# charlieplex12.net
KiCad netlist of a schematic drawn in EAGLE
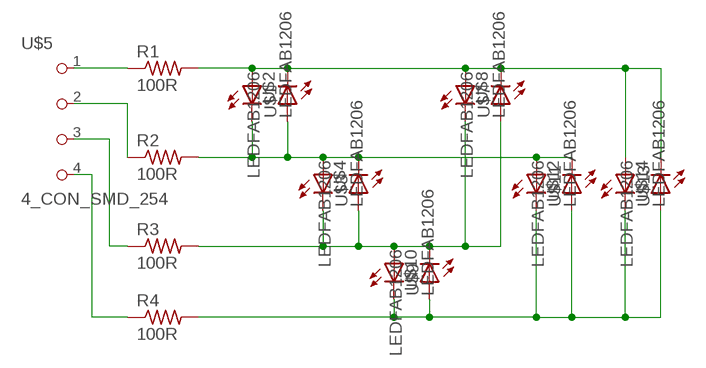
[diagram p0: schematic, sheet 1]

(export (version "E")
  (design (tool "Eeschema 10.0.6"))
  (components
    (comp (ref "R1")
      (value "100R")
      (footprint "eagle-import:R1206FAB")
      (libsource (lib "eagle-import") (part "RES-US1206FAB"))
    )
    (comp (ref "R2")
      (value "100R")
      (footprint "eagle-import:R1206FAB")
      (libsource (lib "eagle-import") (part "RES-US1206FAB"))
    )
    (comp (ref "R3")
      (value "100R")
      (footprint "eagle-import:R1206FAB")
      (libsource (lib "eagle-import") (part "RES-US1206FAB"))
    )
    (comp (ref "R4")
      (value "100R")
      (footprint "eagle-import:R1206FAB")
      (libsource (lib "eagle-import") (part "RES-US1206FAB"))
    )
    (comp (ref "U$1")
      (value "LEDFAB1206")
      (footprint "eagle-import:LED1206FAB")
      (libsource (lib "eagle-import") (part "LEDFAB1206"))
    )
    (comp (ref "U$2")
      (value "LEDFAB1206")
      (footprint "eagle-import:LED1206FAB")
      (libsource (lib "eagle-import") (part "LEDFAB1206"))
    )
    (comp (ref "U$3")
      (value "LEDFAB1206")
      (footprint "eagle-import:LED1206FAB")
      (libsource (lib "eagle-import") (part "LEDFAB1206"))
    )
    (comp (ref "U$4")
      (value "LEDFAB1206")
      (footprint "eagle-import:LED1206FAB")
      (libsource (lib "eagle-import") (part "LEDFAB1206"))
    )
    (comp (ref "U$5")
      (value "4_CON_SMD_254")
      (footprint "eagle-import:4_CON_SMD_254")
      (libsource (lib "eagle-import") (part "4_CON_SMD_254"))
    )
    (comp (ref "U$7")
      (value "LEDFAB1206")
      (footprint "eagle-import:LED1206FAB")
      (libsource (lib "eagle-import") (part "LEDFAB1206"))
    )
    (comp (ref "U$8")
      (value "LEDFAB1206")
      (footprint "eagle-import:LED1206FAB")
      (libsource (lib "eagle-import") (part "LEDFAB1206"))
    )
    (comp (ref "U$9")
      (value "LEDFAB1206")
      (footprint "eagle-import:LED1206FAB")
      (libsource (lib "eagle-import") (part "LEDFAB1206"))
    )
    (comp (ref "U$10")
      (value "LEDFAB1206")
      (footprint "eagle-import:LED1206FAB")
      (libsource (lib "eagle-import") (part "LEDFAB1206"))
    )
    (comp (ref "U$11")
      (value "LEDFAB1206")
      (footprint "eagle-import:LED1206FAB")
      (libsource (lib "eagle-import") (part "LEDFAB1206"))
    )
    (comp (ref "U$12")
      (value "LEDFAB1206")
      (footprint "eagle-import:LED1206FAB")
      (libsource (lib "eagle-import") (part "LEDFAB1206"))
    )
    (comp (ref "U$13")
      (value "LEDFAB1206")
      (footprint "eagle-import:LED1206FAB")
      (libsource (lib "eagle-import") (part "LEDFAB1206"))
    )
    (comp (ref "U$14")
      (value "LEDFAB1206")
      (footprint "eagle-import:LED1206FAB")
      (libsource (lib "eagle-import") (part "LEDFAB1206"))
    )
  )
  (nets
    (net (code "1") (name "Net-(R1-Pad1)") (class "Default")
      (node (ref "R1") (pin "1") (pinfunction "1_1") (pintype "passive"))
      (node (ref "U$5") (pin "1") (pinfunction "1_1") (pintype "passive"))
    )
    (net (code "2") (name "Net-(R2-Pad1)") (class "Default")
      (node (ref "R2") (pin "1") (pinfunction "1_1") (pintype "passive"))
      (node (ref "U$5") (pin "2") (pinfunction "2_2") (pintype "passive"))
    )
    (net (code "3") (name "Net-(R3-Pad1)") (class "Default")
      (node (ref "R3") (pin "1") (pinfunction "1_1") (pintype "passive"))
      (node (ref "U$5") (pin "3") (pinfunction "3_3") (pintype "passive"))
    )
    (net (code "4") (name "Net-(R4-Pad1)") (class "Default")
      (node (ref "R4") (pin "1") (pinfunction "1_1") (pintype "passive"))
      (node (ref "U$5") (pin "4") (pinfunction "4_4") (pintype "passive"))
    )
    (net (code "5") (name "Net-(U$1-A)") (class "Default")
      (node (ref "R1") (pin "2") (pinfunction "2_2") (pintype "passive"))
      (node (ref "U$1") (pin "1") (pinfunction "A_1") (pintype "passive"))
      (node (ref "U$13") (pin "1") (pinfunction "A_1") (pintype "passive"))
      (node (ref "U$14") (pin "2") (pinfunction "C_2") (pintype "passive"))
      (node (ref "U$2") (pin "2") (pinfunction "C_2") (pintype "passive"))
      (node (ref "U$7") (pin "1") (pinfunction "A_1") (pintype "passive"))
      (node (ref "U$8") (pin "2") (pinfunction "C_2") (pintype "passive"))
    )
    (net (code "6") (name "Net-(U$1-C)") (class "Default")
      (node (ref "R2") (pin "2") (pinfunction "2_2") (pintype "passive"))
      (node (ref "U$1") (pin "2") (pinfunction "C_2") (pintype "passive"))
      (node (ref "U$11") (pin "1") (pinfunction "A_1") (pintype "passive"))
      (node (ref "U$12") (pin "2") (pinfunction "C_2") (pintype "passive"))
      (node (ref "U$2") (pin "1") (pinfunction "A_1") (pintype "passive"))
      (node (ref "U$3") (pin "1") (pinfunction "A_1") (pintype "passive"))
      (node (ref "U$4") (pin "2") (pinfunction "C_2") (pintype "passive"))
    )
    (net (code "7") (name "Net-(U$10-A)") (class "Default")
      (node (ref "R4") (pin "2") (pinfunction "2_2") (pintype "passive"))
      (node (ref "U$10") (pin "1") (pinfunction "A_1") (pintype "passive"))
      (node (ref "U$11") (pin "2") (pinfunction "C_2") (pintype "passive"))
      (node (ref "U$12") (pin "1") (pinfunction "A_1") (pintype "passive"))
      (node (ref "U$13") (pin "2") (pinfunction "C_2") (pintype "passive"))
      (node (ref "U$14") (pin "1") (pinfunction "A_1") (pintype "passive"))
      (node (ref "U$9") (pin "2") (pinfunction "C_2") (pintype "passive"))
    )
    (net (code "8") (name "Net-(U$10-C)") (class "Default")
      (node (ref "R3") (pin "2") (pinfunction "2_2") (pintype "passive"))
      (node (ref "U$10") (pin "2") (pinfunction "C_2") (pintype "passive"))
      (node (ref "U$3") (pin "2") (pinfunction "C_2") (pintype "passive"))
      (node (ref "U$4") (pin "1") (pinfunction "A_1") (pintype "passive"))
      (node (ref "U$7") (pin "2") (pinfunction "C_2") (pintype "passive"))
      (node (ref "U$8") (pin "1") (pinfunction "A_1") (pintype "passive"))
      (node (ref "U$9") (pin "1") (pinfunction "A_1") (pintype "passive"))
    )
  )
)
